# FINGER_PRINT.net
KiCad netlist of a schematic drawn in Altium Designer
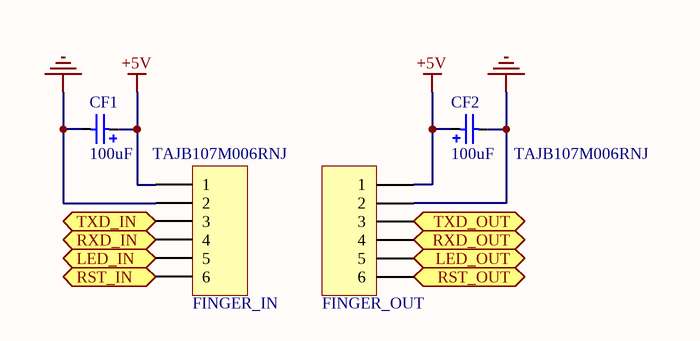
[diagram p0: FINGER_PRINT.SchDoc]

(export (version "E")
  (design (tool "Eeschema 10.0.6"))
  (components
    (comp (ref "CF1")
      (value "100uF     TAJB107M006RNJ")
      (footprint "CAP_TAN_B_3518")
      (description "Capacitor")
      (fields (field (name "Comment") "Cap_Tan"))
      (libsource (lib "Peace的集成库") (part "Cap_Tan"))
    )
    (comp (ref "CF2")
      (value "100uF     TAJB107M006RNJ")
      (footprint "CAP_TAN_B_3518")
      (description "Capacitor")
      (fields (field (name "Comment") "Cap_Tan"))
      (libsource (lib "Peace的集成库") (part "Cap_Tan"))
    )
    (comp (ref "FINGER_IN")
      (value "Header 6")
      (footprint "HX2.54-6")
      (description "Header, 6-Pin")
      (fields (field (name "PUBLISHER") "Altium Limited"))
      (libsource (lib "") (part "Header 6_1"))
    )
    (comp (ref "FINGER_OUT")
      (value "Header 6")
      (footprint "HX2.54-6")
      (description "Header, 6-Pin")
      (fields (field (name "PUBLISHER") "Altium Limited"))
      (libsource (lib "原理图库") (part "Header 6"))
    )
  )
  (nets
    (net (code "1") (name "+5V") (class "Default")
      (node (ref "CF1") (pin "1") (pinfunction "1_1") (pintype "passive"))
      (node (ref "CF2") (pin "1") (pinfunction "1_1") (pintype "passive"))
      (node (ref "FINGER_IN") (pin "1") (pinfunction "1_1") (pintype "passive"))
      (node (ref "FINGER_OUT") (pin "1") (pinfunction "1_1") (pintype "passive"))
    )
    (net (code "2") (name "/LED_IN") (class "Default")
      (node (ref "FINGER_IN") (pin "5") (pinfunction "5_5") (pintype "passive"))
    )
    (net (code "3") (name "/LED_OUT") (class "Default")
      (node (ref "FINGER_OUT") (pin "5") (pinfunction "5_5") (pintype "passive"))
    )
    (net (code "4") (name "/RST_IN") (class "Default")
      (node (ref "FINGER_IN") (pin "6") (pinfunction "6_6") (pintype "passive"))
    )
    (net (code "5") (name "/RST_OUT") (class "Default")
      (node (ref "FINGER_OUT") (pin "6") (pinfunction "6_6") (pintype "passive"))
    )
    (net (code "6") (name "/RXD_IN") (class "Default")
      (node (ref "FINGER_IN") (pin "4") (pinfunction "4_4") (pintype "passive"))
    )
    (net (code "7") (name "/RXD_OUT") (class "Default")
      (node (ref "FINGER_OUT") (pin "4") (pinfunction "4_4") (pintype "passive"))
    )
    (net (code "8") (name "/TXD_IN") (class "Default")
      (node (ref "FINGER_IN") (pin "3") (pinfunction "3_3") (pintype "passive"))
    )
    (net (code "9") (name "/TXD_OUT") (class "Default")
      (node (ref "FINGER_OUT") (pin "3") (pinfunction "3_3") (pintype "passive"))
    )
    (net (code "10") (name "GND") (class "Default")
      (node (ref "CF1") (pin "2") (pinfunction "2_2") (pintype "passive"))
      (node (ref "CF2") (pin "2") (pinfunction "2_2") (pintype "passive"))
      (node (ref "FINGER_IN") (pin "2") (pinfunction "2_2") (pintype "passive"))
      (node (ref "FINGER_OUT") (pin "2") (pinfunction "2_2") (pintype "passive"))
    )
  )
)
